# Schematic_V1.net
KiCad netlist of a schematic drawn in EAGLE
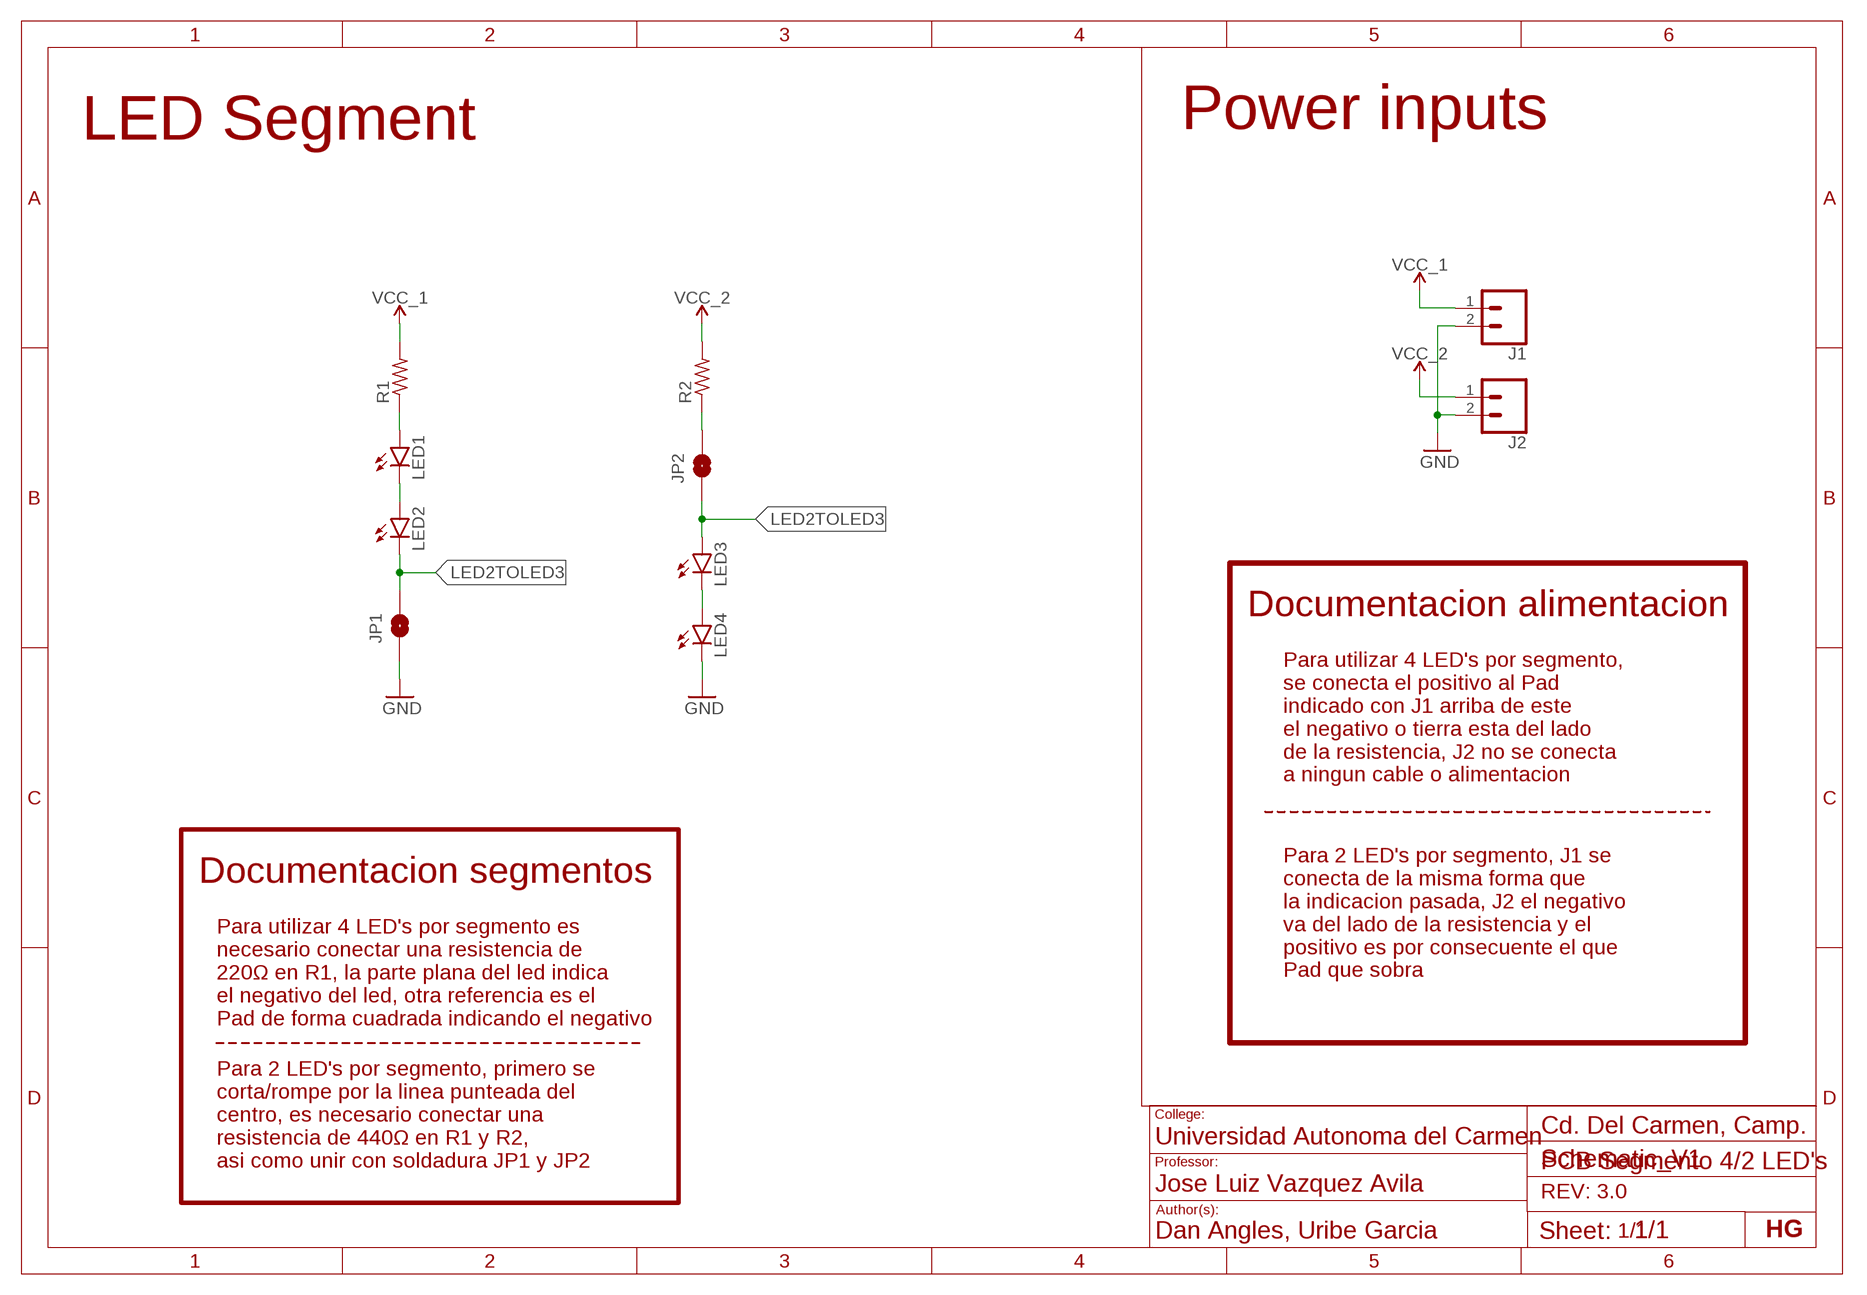
[diagram p0: schematic, sheet 1]

(export (version "E")
  (design (tool "Eeschema 10.0.6"))
  (components
    (comp (ref "J1")
      (value "CONN_02LOCK")
      (footprint "eagle-import:1X02_LOCK")
      (libsource (lib "eagle-import") (part "CONN_02LOCK"))
    )
    (comp (ref "J2")
      (value "CONN_02LOCK")
      (footprint "eagle-import:1X02_LOCK")
      (libsource (lib "eagle-import") (part "CONN_02LOCK"))
    )
    (comp (ref "JP1")
      (value "JUMPER-SMT_2_NO_SILK_ROUND")
      (footprint "eagle-import:SMT-JUMPER_2_NO_SILK_ROUND")
      (libsource (lib "eagle-import") (part "JUMPER-SMT_2_NO_SILK_ROUND"))
    )
    (comp (ref "JP2")
      (value "JUMPER-SMT_2_NO_SILK_ROUND")
      (footprint "eagle-import:SMT-JUMPER_2_NO_SILK_ROUND")
      (libsource (lib "eagle-import") (part "JUMPER-SMT_2_NO_SILK_ROUND"))
    )
    (comp (ref "LED1")
      (value "LED10MM")
      (footprint "eagle-import:LED10MM")
      (libsource (lib "eagle-import") (part "LED10MM"))
    )
    (comp (ref "LED2")
      (value "LED10MM")
      (footprint "eagle-import:LED10MM")
      (libsource (lib "eagle-import") (part "LED10MM"))
    )
    (comp (ref "LED3")
      (value "LED10MM")
      (footprint "eagle-import:LED10MM")
      (libsource (lib "eagle-import") (part "LED10MM"))
    )
    (comp (ref "LED4")
      (value "LED10MM")
      (footprint "eagle-import:LED10MM")
      (libsource (lib "eagle-import") (part "LED10MM"))
    )
    (comp (ref "R1")
      (value "R-US_0411/3V")
      (footprint "eagle-import:0411V")
      (libsource (lib "eagle-import") (part "R-US_0411/3V"))
    )
    (comp (ref "R2")
      (value "R-US_0411/3V")
      (footprint "eagle-import:0411V")
      (libsource (lib "eagle-import") (part "R-US_0411/3V"))
    )
  )
  (nets
    (net (code "1") (name "GND") (class "Default")
      (node (ref "J1") (pin "2") (pinfunction "2_2") (pintype "passive"))
      (node (ref "J2") (pin "2") (pinfunction "2_2") (pintype "passive"))
      (node (ref "JP1") (pin "1") (pinfunction "1_1") (pintype "passive"))
      (node (ref "LED4") (pin "K") (pinfunction "C_K") (pintype "passive"))
    )
    (net (code "2") (name "LED2TOLED3") (class "Default")
      (node (ref "JP1") (pin "2") (pinfunction "2_2") (pintype "passive"))
      (node (ref "JP2") (pin "1") (pinfunction "1_1") (pintype "passive"))
      (node (ref "LED2") (pin "K") (pinfunction "C_K") (pintype "passive"))
      (node (ref "LED3") (pin "A") (pinfunction "A_A") (pintype "passive"))
    )
    (net (code "3") (name "Net-(JP2-Pad2)") (class "Default")
      (node (ref "JP2") (pin "2") (pinfunction "2_2") (pintype "passive"))
      (node (ref "R2") (pin "1") (pinfunction "1_1") (pintype "passive"))
    )
    (net (code "4") (name "Net-(LED1-C)") (class "Default")
      (node (ref "LED1") (pin "K") (pinfunction "C_K") (pintype "passive"))
      (node (ref "LED2") (pin "A") (pinfunction "A_A") (pintype "passive"))
    )
    (net (code "5") (name "Net-(LED1-PadA)") (class "Default")
      (node (ref "LED1") (pin "A") (pinfunction "A_A") (pintype "passive"))
      (node (ref "R1") (pin "1") (pinfunction "1_1") (pintype "passive"))
    )
    (net (code "6") (name "Net-(LED3-C)") (class "Default")
      (node (ref "LED3") (pin "K") (pinfunction "C_K") (pintype "passive"))
      (node (ref "LED4") (pin "A") (pinfunction "A_A") (pintype "passive"))
    )
    (net (code "7") (name "VCC_1") (class "Default")
      (node (ref "J1") (pin "1") (pinfunction "1_1") (pintype "passive"))
      (node (ref "R1") (pin "2") (pinfunction "2_2") (pintype "passive"))
    )
    (net (code "8") (name "VCC_2") (class "Default")
      (node (ref "J2") (pin "1") (pinfunction "1_1") (pintype "passive"))
      (node (ref "R2") (pin "2") (pinfunction "2_2") (pintype "passive"))
    )
  )
)
